# BMS-S03-V00-CellInterface.net
KiCad netlist of a schematic drawn in Altium Designer
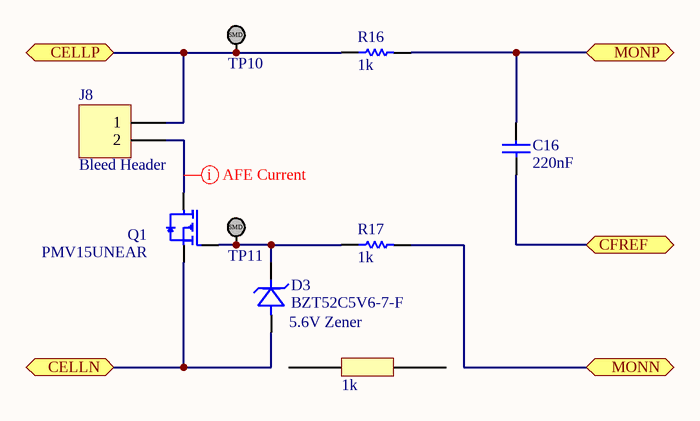
[diagram p0: BMS-S03-V00-CellInterface.SchDoc]

(export (version "E")
  (design (tool "Eeschema 10.0.6"))
  (components
    (comp (ref "C16")
      (value "220nF")
      (footprint "Cap_Ceramic_0603")
      (description "Capacitor, Ceramic, SMD, 220nF, 50V, 5%, X7R, 0603")
      (libsource (lib "StandardCapacitors") (part "220nF 50V 5% X7R 0603"))
    )
    (comp (ref "D3")
      (value "BZT52C5V6-7-F")
      (footprint "SOD123")
      (description "Diode, SMD, Zender, 5.6V, 7%, 500mW, SOD-123")
      (fields (field (name "MANUFACTURER") "Generic") (field (name "MPN") "1.8V 500mW"))
      (libsource (lib "QUTMS_DiodeLibrary") (part "BZT52C5V6-7-F"))
    )
    (comp (ref "J8")
      (value "Bleed Header")
      (footprint "HDR1X2")
      (description "Header, 2-Pin")
      (fields (field (name "PUBLISHER") "Altium Limited"))
      (libsource (lib "Miscellaneous Connectors") (part "Header 2"))
    )
    (comp (ref "Q1")
      (value "MOSFET N")
      (footprint "PMV15UNEAR")
      (description "MOSFET N-CH, 20V, SOT23")
      (fields (field (name "MANUFACTURER") "Nexperia") (field (name "MANUFACTURER PART NUMBER") "PMV15UNEAR"))
      (libsource (lib "CellMonitor") (part "PMV15UNEAR"))
    )
    (comp (ref "R16")
      (value "1k")
      (footprint "Res_ThinFilm_0603")
      (description "Resistor, SMD, 1k, 0.1W, 5%, 0603")
      (libsource (lib "StandardResistors") (part "1k 5% 0603"))
    )
    (comp (ref "R17")
      (value "1k")
      (footprint "Res_ThinFilm_0603")
      (description "Resistor, SMD, 1k, 0.1W, 5%, 0603")
      (libsource (lib "StandardResistors") (part "1k 5% 0603"))
    )
    (comp (ref "TP10")
      (value "TestPoint_SMD")
      (footprint "TestPointSMD")
      (libsource (lib "StandardTest") (part "TestPoint_SMD"))
    )
    (comp (ref "TP11")
      (value "TestPoint_SMD")
      (footprint "TestPointSMD")
      (libsource (lib "StandardTest") (part "TestPoint_SMD"))
    )
  )
  (nets
    (net (code "1") (name "/CELLN") (class "Default")
      (node (ref "D3") (pin "A") (pinfunction "Anode_A") (pintype "passive"))
      (node (ref "Q1") (pin "S") (pinfunction "Source_S") (pintype "passive"))
    )
    (net (code "2") (name "/CELLP") (class "Default")
      (node (ref "J8") (pin "1") (pinfunction "1_1") (pintype "passive"))
      (node (ref "R16") (pin "1") (pinfunction "1_1") (pintype "passive"))
      (node (ref "TP10") (pin "1") (pinfunction "1_1") (pintype "passive"))
    )
    (net (code "3") (name "/CFREF") (class "Default")
      (node (ref "C16") (pin "1") (pinfunction "1_1") (pintype "passive"))
    )
    (net (code "4") (name "/MONN") (class "Default")
      (node (ref "R17") (pin "2") (pinfunction "2_2") (pintype "passive"))
    )
    (net (code "5") (name "/MONP") (class "Default")
      (node (ref "C16") (pin "2") (pinfunction "2_2") (pintype "passive"))
      (node (ref "R16") (pin "2") (pinfunction "2_2") (pintype "passive"))
    )
    (net (code "6") (name "Net-(D3-Cathode)") (class "Default")
      (node (ref "D3") (pin "K") (pinfunction "Cathode_K") (pintype "passive"))
      (node (ref "Q1") (pin "G") (pinfunction "Gate_G") (pintype "passive"))
      (node (ref "R17") (pin "1") (pinfunction "1_1") (pintype "passive"))
      (node (ref "TP11") (pin "1") (pinfunction "1_1") (pintype "passive"))
    )
    (net (code "7") (name "Net-(Q1-Drain)") (class "Default")
      (node (ref "J8") (pin "2") (pinfunction "2_2") (pintype "passive"))
      (node (ref "Q1") (pin "D") (pinfunction "Drain_D") (pintype "passive"))
    )
  )
)
